# Additions.net
KiCad netlist of a schematic drawn in Altium Designer
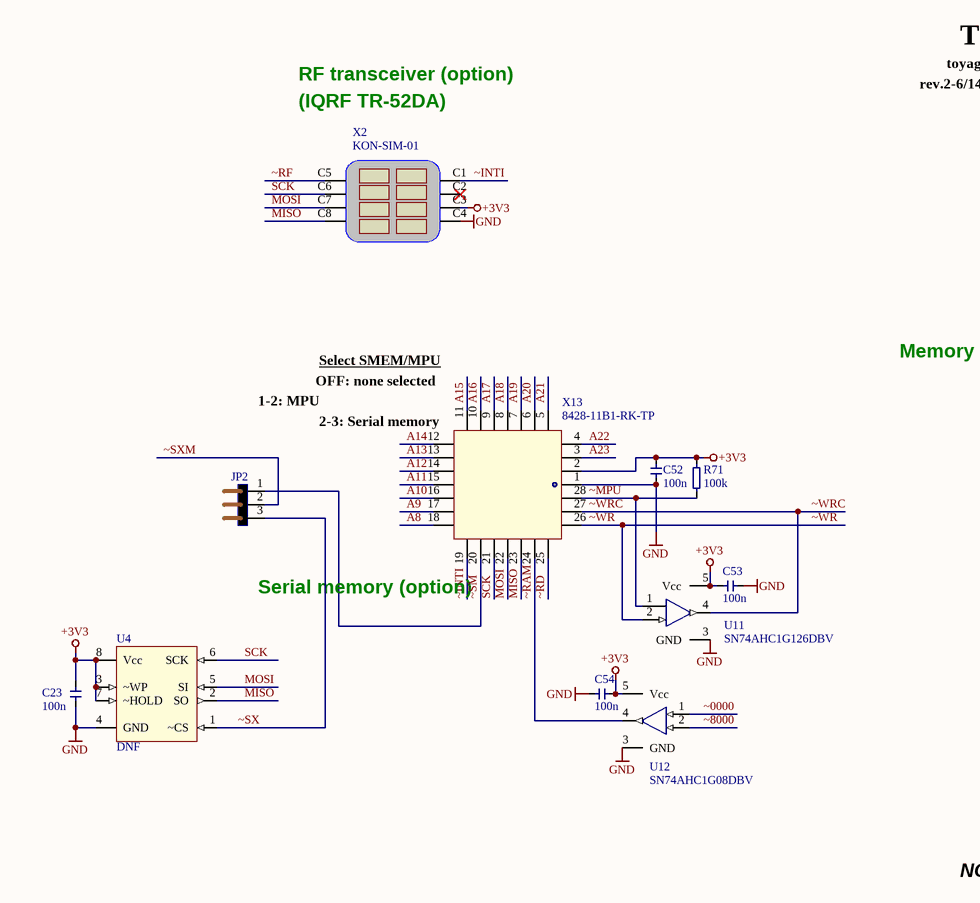
[diagram p0: Additions.SchDoc]

(export (version "E")
  (design (tool "Eeschema 10.0.6"))
  (components
    (comp (ref "C23")
      (value "100n")
      (footprint "_0805")
      (description "Capacitor")
      (libsource (lib "Discretes") (part "Capacitor"))
    )
    (comp (ref "C52")
      (value "100n")
      (footprint "_0805")
      (description "Capacitor")
      (libsource (lib "Discretes") (part "Capacitor"))
    )
    (comp (ref "C53")
      (value "100n")
      (footprint "_0805")
      (description "Capacitor")
      (libsource (lib "Discretes") (part "Capacitor"))
    )
    (comp (ref "C54")
      (value "100n")
      (footprint "_0805")
      (description "Capacitor")
      (libsource (lib "Discretes") (part "Capacitor"))
    )
    (comp (ref "JP2")
      (value "Jumper 3")
      (footprint "2011-1X03S")
      (description "2.54mm square pin header/jumper")
      (libsource (lib "Connectors") (part "Jumper 3"))
    )
    (comp (ref "R71")
      (value "100k")
      (footprint "_0805")
      (description "Resistor")
      (libsource (lib "Discretes") (part "Resistor"))
    )
    (comp (ref "U4")
      (value "DNF")
      (footprint "SOIC127P760-8N")
      (description "Standard 8-pin SPI flash memory")
      (libsource (lib "IC Other Functions") (part "SPI Flash 8pin"))
    )
    (comp (ref "U11")
      (value "SN74AHC1G126DBV")
      (footprint "SOT23-5")
      (description "Buffer gate with non-invertinng Enable input")
      (fields (field (name "MANUFACTURER") "Texas Instruments"))
      (libsource (lib "16Z") (part "SN74xxx1G126"))
    )
    (comp (ref "U12")
      (value "SN74AHC1G08DBV")
      (footprint "SOT23-5")
      (description "2-INPUT AND GATE")
      (fields (field (name "MANUFACTURER") "Texas Instruments"))
      (libsource (lib "IC Logic") (part "SN74xxx1G08"))
    )
    (comp (ref "X2")
      (value "KON-SIM-01")
      (footprint "KON-SIM-01")
      (description "SIM/microSIM 6-pin connector")
      (libsource (lib "Connectors") (part "SIM/microSIM (8-pin)"))
    )
    (comp (ref "X13")
      (value "8428-11B1-RK-TP")
      (footprint "PLCC28-T/H socket")
      (description "PLCC28 T/H socket")
      (libsource (lib "Connectors") (part "PLCC28 socket"))
    )
  )
  (nets
    (net (code "1") (name "+3V3") (class "Default")
      (node (ref "C23") (pin "1") (pintype "passive"))
      (node (ref "C52") (pin "1") (pintype "passive"))
      (node (ref "C53") (pin "1") (pintype "passive"))
      (node (ref "C54") (pin "2") (pintype "passive"))
      (node (ref "R71") (pin "2") (pintype "passive"))
      (node (ref "U11") (pin "5") (pinfunction "Vcc_5") (pintype "power_in"))
      (node (ref "U12") (pin "5") (pinfunction "Vcc_5") (pintype "power_in"))
      (node (ref "U4") (pin "3") (pinfunction "~WP_3") (pintype "input"))
      (node (ref "U4") (pin "7") (pinfunction "~HOLD_7") (pintype "input"))
      (node (ref "U4") (pin "8") (pinfunction "Vcc_8") (pintype "power_in"))
      (node (ref "X13") (pin "2") (pintype "passive"))
      (node (ref "X2") (pin "C3") (pintype "passive"))
    )
    (net (code "2") (name "/A8") (class "Default") (node (ref "X13") (pin "18") (pintype "passive")))
    (net (code "3") (name "/A9") (class "Default") (node (ref "X13") (pin "17") (pintype "passive")))
    (net (code "4") (name "/A10") (class "Default") (node (ref "X13") (pin "16") (pintype "passive")))
    (net (code "5") (name "/A11") (class "Default") (node (ref "X13") (pin "15") (pintype "passive")))
    (net (code "6") (name "/A12") (class "Default") (node (ref "X13") (pin "14") (pintype "passive")))
    (net (code "7") (name "/A13") (class "Default") (node (ref "X13") (pin "13") (pintype "passive")))
    (net (code "8") (name "/A14") (class "Default") (node (ref "X13") (pin "12") (pintype "passive")))
    (net (code "9") (name "/A15") (class "Default") (node (ref "X13") (pin "11") (pintype "passive")))
    (net (code "10") (name "/A16") (class "Default") (node (ref "X13") (pin "10") (pintype "passive")))
    (net (code "11") (name "/A17") (class "Default") (node (ref "X13") (pin "9") (pintype "passive")))
    (net (code "12") (name "/A18") (class "Default") (node (ref "X13") (pin "8") (pintype "passive")))
    (net (code "13") (name "/A19") (class "Default") (node (ref "X13") (pin "7") (pintype "passive")))
    (net (code "14") (name "/A20") (class "Default") (node (ref "X13") (pin "6") (pintype "passive")))
    (net (code "15") (name "/A21") (class "Default") (node (ref "X13") (pin "5") (pintype "passive")))
    (net (code "16") (name "/A22") (class "Default") (node (ref "X13") (pin "4") (pintype "passive")))
    (net (code "17") (name "/A23") (class "Default") (node (ref "X13") (pin "3") (pintype "passive")))
    (net (code "18") (name "/MISO") (class "Default")
      (node (ref "U4") (pin "2") (pinfunction "SO_2") (pintype "output"))
      (node (ref "X13") (pin "23") (pintype "passive"))
      (node (ref "X2") (pin "C8") (pintype "passive"))
    )
    (net (code "19") (name "/MOSI") (class "Default")
      (node (ref "U4") (pin "5") (pinfunction "SI_5") (pintype "input"))
      (node (ref "X13") (pin "22") (pintype "passive"))
      (node (ref "X2") (pin "C7") (pintype "passive"))
    )
    (net (code "20") (name "/SCK") (class "Default")
      (node (ref "U4") (pin "6") (pinfunction "SCK_6") (pintype "input"))
      (node (ref "X13") (pin "21") (pintype "passive"))
      (node (ref "X2") (pin "C6") (pintype "passive"))
    )
    (net (code "21") (name "/~0000") (class "Default") (node (ref "U12") (pin "1") (pintype "input")))
    (net (code "22") (name "/~8000") (class "Default") (node (ref "U12") (pin "2") (pintype "input")))
    (net (code "23") (name "/~INTI") (class "Default")
      (node (ref "X13") (pin "19") (pintype "passive"))
      (node (ref "X2") (pin "C1") (pintype "passive"))
    )
    (net (code "24") (name "/~MPU") (class "Default")
      (node (ref "R71") (pin "1") (pintype "passive"))
      (node (ref "U11") (pin "1") (pinfunction "OE_1") (pintype "passive"))
      (node (ref "X13") (pin "28") (pintype "passive"))
    )
    (net (code "25") (name "/~RAM") (class "Default")
      (node (ref "U12") (pin "4") (pintype "output"))
      (node (ref "X13") (pin "24") (pintype "passive"))
    )
    (net (code "26") (name "/~RD") (class "Default") (node (ref "X13") (pin "25") (pintype "passive")))
    (net (code "27") (name "/~RF") (class "Default") (node (ref "X2") (pin "C5") (pintype "passive")))
    (net (code "28") (name "/~SM") (class "Default")
      (node (ref "JP2") (pin "1") (pintype "passive"))
      (node (ref "X13") (pin "20") (pintype "passive"))
    )
    (net (code "29") (name "/~SX") (class "Default")
      (node (ref "JP2") (pin "3") (pintype "passive"))
      (node (ref "U4") (pin "1") (pinfunction "~CS_1") (pintype "input"))
    )
    (net (code "30") (name "/~SXM") (class "Default") (node (ref "JP2") (pin "2") (pintype "passive")))
    (net (code "31") (name "/~WR") (class "Default")
      (node (ref "U11") (pin "2") (pinfunction "A_2") (pintype "input"))
      (node (ref "X13") (pin "26") (pintype "passive"))
    )
    (net (code "32") (name "/~WRC") (class "Default")
      (node (ref "U11") (pin "4") (pintype "output"))
      (node (ref "X13") (pin "27") (pintype "passive"))
    )
    (net (code "33") (name "GND") (class "Default")
      (node (ref "C23") (pin "2") (pintype "passive"))
      (node (ref "C52") (pin "2") (pintype "passive"))
      (node (ref "C53") (pin "2") (pintype "passive"))
      (node (ref "C54") (pin "1") (pintype "passive"))
      (node (ref "U11") (pin "3") (pinfunction "GND_3") (pintype "power_in"))
      (node (ref "U12") (pin "3") (pinfunction "GND_3") (pintype "power_in"))
      (node (ref "U4") (pin "4") (pinfunction "GND_4") (pintype "power_in"))
      (node (ref "X13") (pin "1") (pintype "passive"))
      (node (ref "X2") (pin "C4") (pintype "passive"))
    )
    (net (code "34") (name "unconnected-(X2-PadC2)") (class "Default")
      (node (ref "X2") (pin "C2") (pintype "passive+no_connect"))
    )
  )
)
